# Connectors.net
KiCad netlist of a schematic drawn in Altium Designer
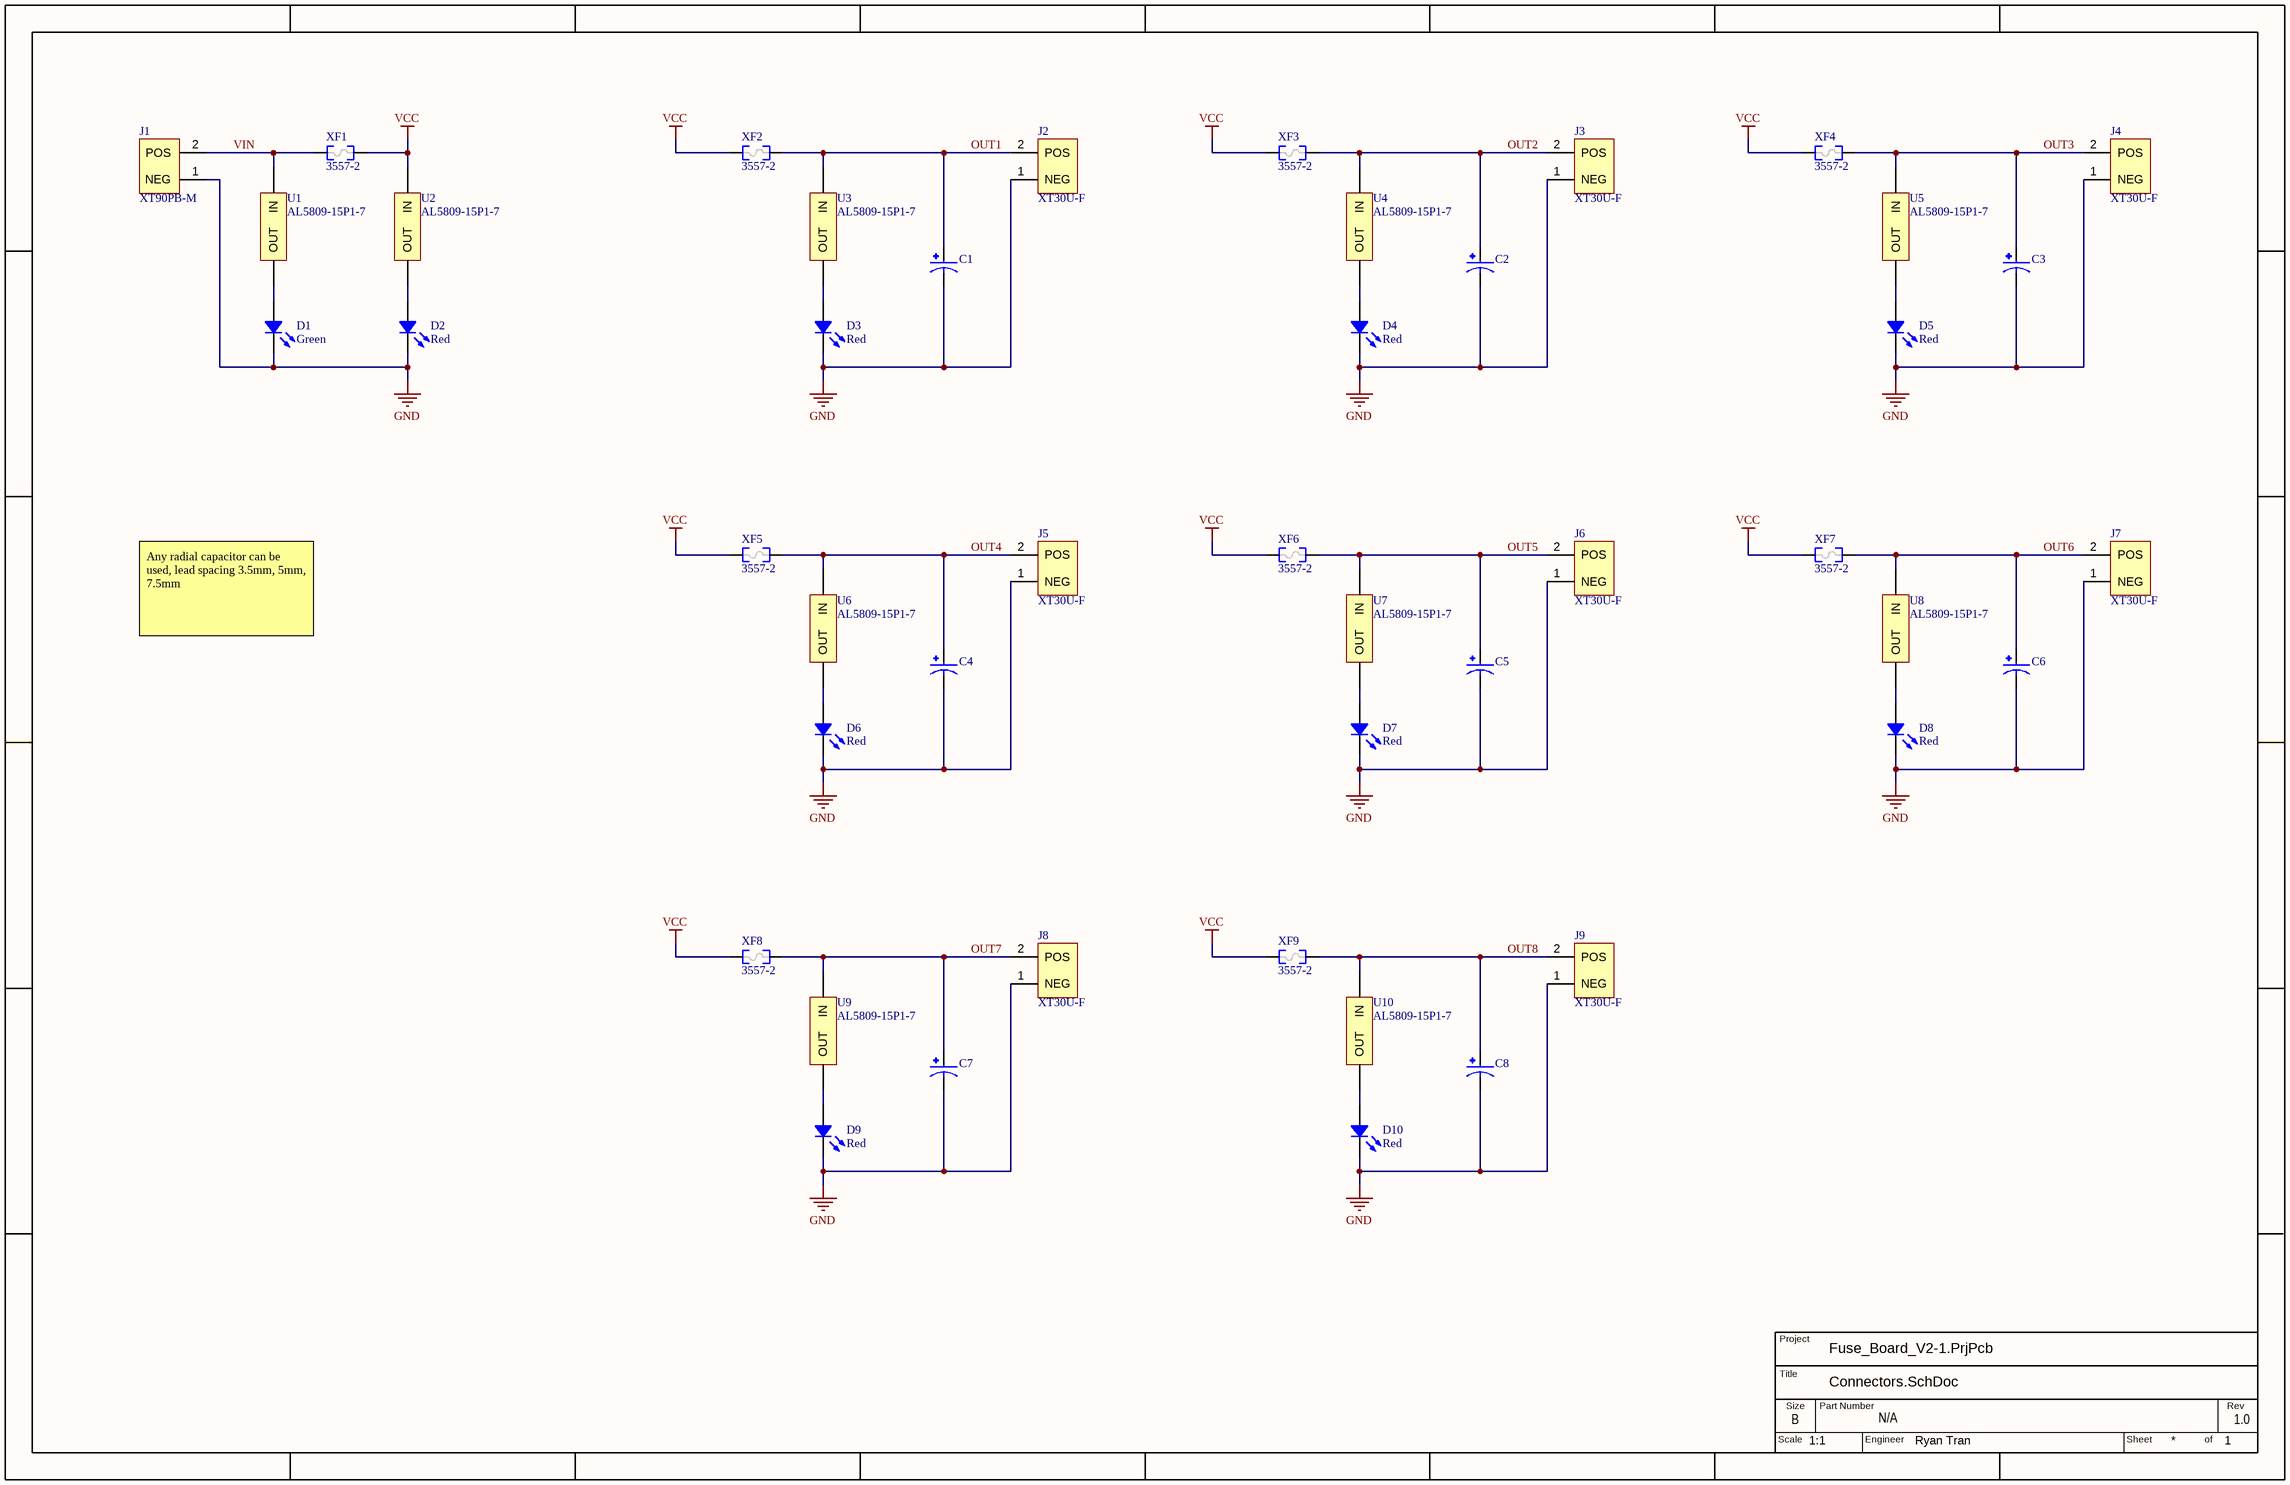
[diagram p0: Connectors.SchDoc]

(export (version "E")
  (design (tool "Eeschema 10.0.6"))
  (components
    (comp (ref "C1")
      (value "Capacitor Generic")
      (footprint "RADIAL_CAP_10mm")
      (description "Cap Radial Aluminum Cylindrical Can 3.5mm, 5mm")
      (fields (field (name "MF") "Panasonic") (field (name "MP") "ECA-2WHG220"))
      (libsource (lib "Fuse_Board_Symbols") (part "Capacitor Generic"))
    )
    (comp (ref "C2")
      (value "Capacitor Generic")
      (footprint "RADIAL_CAP_10mm")
      (description "Cap Radial Aluminum Cylindrical Can 3.5mm, 5mm")
      (fields (field (name "MF") "Panasonic") (field (name "MP") "ECA-2WHG220"))
      (libsource (lib "Fuse_Board_Symbols") (part "Capacitor Generic"))
    )
    (comp (ref "C3")
      (value "Capacitor Generic")
      (footprint "RADIAL_CAP_10mm")
      (description "Cap Radial Aluminum Cylindrical Can 3.5mm, 5mm")
      (fields (field (name "MF") "Panasonic") (field (name "MP") "ECA-2WHG220"))
      (libsource (lib "Fuse_Board_Symbols") (part "Capacitor Generic"))
    )
    (comp (ref "C4")
      (value "Capacitor Generic")
      (footprint "RADIAL_CAP_10mm")
      (description "Cap Radial Aluminum Cylindrical Can 3.5mm, 5mm")
      (fields (field (name "MF") "Panasonic") (field (name "MP") "ECA-2WHG220"))
      (libsource (lib "Fuse_Board_Symbols") (part "Capacitor Generic"))
    )
    (comp (ref "C5")
      (value "Capacitor Generic")
      (footprint "RADIAL_CAP_10mm")
      (description "Cap Radial Aluminum Cylindrical Can 3.5mm, 5mm")
      (fields (field (name "MF") "Panasonic") (field (name "MP") "ECA-2WHG220"))
      (libsource (lib "Fuse_Board_Symbols") (part "Capacitor Generic"))
    )
    (comp (ref "C6")
      (value "Capacitor Generic")
      (footprint "RADIAL_CAP_10mm")
      (description "Cap Radial Aluminum Cylindrical Can 3.5mm, 5mm")
      (fields (field (name "MF") "Panasonic") (field (name "MP") "ECA-2WHG220"))
      (libsource (lib "Fuse_Board_Symbols") (part "Capacitor Generic"))
    )
    (comp (ref "C7")
      (value "Capacitor Generic")
      (footprint "RADIAL_CAP_10mm")
      (description "Cap Radial Aluminum Cylindrical Can 3.5mm, 5mm")
      (fields (field (name "MF") "Panasonic") (field (name "MP") "ECA-2WHG220"))
      (libsource (lib "Fuse_Board_Symbols") (part "Capacitor Generic"))
    )
    (comp (ref "C8")
      (value "Capacitor Generic")
      (footprint "RADIAL_CAP_10mm")
      (description "Cap Radial Aluminum Cylindrical Can 3.5mm, 5mm")
      (fields (field (name "MF") "Panasonic") (field (name "MP") "ECA-2WHG220"))
      (libsource (lib "Fuse_Board_Symbols") (part "Capacitor Generic"))
    )
    (comp (ref "D1")
      (value "Green")
      (footprint "LED 0603_1608 GREEN")
      (description "LED GREEN CLEAR CHIP SMD")
      (fields (field (name "PART NUMBER") "LTST-C193TGKT-5A") (field (name "MANUFACTURER") "Lite-On Inc."))
      (libsource (lib "Celestial Altium Library - altium_library") (part "LED"))
    )
    (comp (ref "D2")
      (value "Red")
      (footprint "LED 0603_1608 RED")
      (description "LED RED CLEAR 2SMD")
      (fields
        (field (name "PART NUMBER") "19-217/R6C-AL1M2VY/3T")
        (field (name "MANUFACTURER") "Everlight Electronics Co Ltd")
      )
      (libsource (lib "Celestial Altium Library - altium_library") (part "LED"))
    )
    (comp (ref "D3")
      (value "Red")
      (footprint "LED 0603_1608 RED")
      (description "LED RED CLEAR 2SMD")
      (fields
        (field (name "PART NUMBER") "19-217/R6C-AL1M2VY/3T")
        (field (name "MANUFACTURER") "Everlight Electronics Co Ltd")
      )
      (libsource (lib "Celestial Altium Library - altium_library") (part "LED"))
    )
    (comp (ref "D4")
      (value "Red")
      (footprint "LED 0603_1608 RED")
      (description "LED RED CLEAR 2SMD")
      (fields
        (field (name "PART NUMBER") "19-217/R6C-AL1M2VY/3T")
        (field (name "MANUFACTURER") "Everlight Electronics Co Ltd")
      )
      (libsource (lib "Celestial Altium Library - altium_library") (part "LED"))
    )
    (comp (ref "D5")
      (value "Red")
      (footprint "LED 0603_1608 RED")
      (description "LED RED CLEAR 2SMD")
      (fields
        (field (name "PART NUMBER") "19-217/R6C-AL1M2VY/3T")
        (field (name "MANUFACTURER") "Everlight Electronics Co Ltd")
      )
      (libsource (lib "Celestial Altium Library - altium_library") (part "LED"))
    )
    (comp (ref "D6")
      (value "Red")
      (footprint "LED 0603_1608 RED")
      (description "LED RED CLEAR 2SMD")
      (fields
        (field (name "PART NUMBER") "19-217/R6C-AL1M2VY/3T")
        (field (name "MANUFACTURER") "Everlight Electronics Co Ltd")
      )
      (libsource (lib "Celestial Altium Library - altium_library") (part "LED"))
    )
    (comp (ref "D7")
      (value "Red")
      (footprint "LED 0603_1608 RED")
      (description "LED RED CLEAR 2SMD")
      (fields
        (field (name "PART NUMBER") "19-217/R6C-AL1M2VY/3T")
        (field (name "MANUFACTURER") "Everlight Electronics Co Ltd")
      )
      (libsource (lib "Celestial Altium Library - altium_library") (part "LED"))
    )
    (comp (ref "D8")
      (value "Red")
      (footprint "LED 0603_1608 RED")
      (description "LED RED CLEAR 2SMD")
      (fields
        (field (name "PART NUMBER") "19-217/R6C-AL1M2VY/3T")
        (field (name "MANUFACTURER") "Everlight Electronics Co Ltd")
      )
      (libsource (lib "Celestial Altium Library - altium_library") (part "LED"))
    )
    (comp (ref "D9")
      (value "Red")
      (footprint "LED 0603_1608 RED")
      (description "LED RED CLEAR 2SMD")
      (fields
        (field (name "PART NUMBER") "19-217/R6C-AL1M2VY/3T")
        (field (name "MANUFACTURER") "Everlight Electronics Co Ltd")
      )
      (libsource (lib "Celestial Altium Library - altium_library") (part "LED"))
    )
    (comp (ref "D10")
      (value "Red")
      (footprint "LED 0603_1608 RED")
      (description "LED RED CLEAR 2SMD")
      (fields
        (field (name "PART NUMBER") "19-217/R6C-AL1M2VY/3T")
        (field (name "MANUFACTURER") "Everlight Electronics Co Ltd")
      )
      (libsource (lib "Celestial Altium Library - altium_library") (part "LED"))
    )
    (comp (ref "J1")
      (value "XT90PB-M")
      (footprint "XT90PB-M")
      (description "Plug; DC supply; XT90; male; PIN: 2; for cable; soldered; 30A; 500V")
      (fields (field (name "MP") "XT60-M") (field (name "MF") "AMASS"))
      (libsource (lib "Fuse_Board_Symbols") (part "XT90PB-M"))
    )
    (comp (ref "J2")
      (value "XT30U-F")
      (footprint "AMASS_XT30UPB")
      (description "Plug; DC supply; XT30; female; PIN: 2; for cable; soldering; 15A")
      (fields (field (name "MP") "XT60-M") (field (name "MF") "AMASS"))
      (libsource (lib "Fuse_Board_Symbols_V2-1") (part "XT30U-F"))
    )
    (comp (ref "J3")
      (value "XT30U-F")
      (footprint "AMASS_XT30UPB")
      (description "Plug; DC supply; XT30; female; PIN: 2; for cable; soldering; 15A")
      (fields (field (name "MP") "XT60-M") (field (name "MF") "AMASS"))
      (libsource (lib "Fuse_Board_Symbols_V2-1") (part "XT30U-F"))
    )
    (comp (ref "J4")
      (value "XT30U-F")
      (footprint "AMASS_XT30UPB")
      (description "Plug; DC supply; XT30; female; PIN: 2; for cable; soldering; 15A")
      (fields (field (name "MP") "XT60-M") (field (name "MF") "AMASS"))
      (libsource (lib "Fuse_Board_Symbols_V2-1") (part "XT30U-F"))
    )
    (comp (ref "J5")
      (value "XT30U-F")
      (footprint "AMASS_XT30UPB")
      (description "Plug; DC supply; XT30; female; PIN: 2; for cable; soldering; 15A")
      (fields (field (name "MP") "XT60-M") (field (name "MF") "AMASS"))
      (libsource (lib "Fuse_Board_Symbols_V2-1") (part "XT30U-F"))
    )
    (comp (ref "J6")
      (value "XT30U-F")
      (footprint "AMASS_XT30UPB")
      (description "Plug; DC supply; XT30; female; PIN: 2; for cable; soldering; 15A")
      (fields (field (name "MP") "XT60-M") (field (name "MF") "AMASS"))
      (libsource (lib "Fuse_Board_Symbols_V2-1") (part "XT30U-F"))
    )
    (comp (ref "J7")
      (value "XT30U-F")
      (footprint "AMASS_XT30UPB")
      (description "Plug; DC supply; XT30; female; PIN: 2; for cable; soldering; 15A")
      (fields (field (name "MP") "XT60-M") (field (name "MF") "AMASS"))
      (libsource (lib "Fuse_Board_Symbols_V2-1") (part "XT30U-F"))
    )
    (comp (ref "J8")
      (value "XT30U-F")
      (footprint "AMASS_XT30UPB")
      (description "Plug; DC supply; XT30; female; PIN: 2; for cable; soldering; 15A")
      (fields (field (name "MP") "XT60-M") (field (name "MF") "AMASS"))
      (libsource (lib "Fuse_Board_Symbols_V2-1") (part "XT30U-F"))
    )
    (comp (ref "J9")
      (value "XT30U-F")
      (footprint "AMASS_XT30UPB")
      (description "Plug; DC supply; XT30; female; PIN: 2; for cable; soldering; 15A")
      (fields (field (name "MP") "XT60-M") (field (name "MF") "AMASS"))
      (libsource (lib "Fuse_Board_Symbols_V2-1") (part "XT30U-F"))
    )
    (comp (ref "U1")
      (value "AL5809-15P1-7")
      (footprint "POWERDI_123")
      (description "LED Driver IC 1 Output Linear - PWM Dimming 15mA PowerDI™ 123")
      (libsource (lib "Fuse_Board_Symbols") (part "AL5809-15P1-7"))
    )
    (comp (ref "U2")
      (value "AL5809-15P1-7")
      (footprint "POWERDI_123")
      (description "LED Driver IC 1 Output Linear - PWM Dimming 15mA PowerDI™ 123")
      (libsource (lib "Fuse_Board_Symbols") (part "AL5809-15P1-7"))
    )
    (comp (ref "U3")
      (value "AL5809-15P1-7")
      (footprint "POWERDI_123")
      (description "LED Driver IC 1 Output Linear - PWM Dimming 15mA PowerDI™ 123")
      (libsource (lib "Fuse_Board_Symbols") (part "AL5809-15P1-7"))
    )
    (comp (ref "U4")
      (value "AL5809-15P1-7")
      (footprint "POWERDI_123")
      (description "LED Driver IC 1 Output Linear - PWM Dimming 15mA PowerDI™ 123")
      (libsource (lib "Fuse_Board_Symbols") (part "AL5809-15P1-7"))
    )
    (comp (ref "U5")
      (value "AL5809-15P1-7")
      (footprint "POWERDI_123")
      (description "LED Driver IC 1 Output Linear - PWM Dimming 15mA PowerDI™ 123")
      (libsource (lib "Fuse_Board_Symbols") (part "AL5809-15P1-7"))
    )
    (comp (ref "U6")
      (value "AL5809-15P1-7")
      (footprint "POWERDI_123")
      (description "LED Driver IC 1 Output Linear - PWM Dimming 15mA PowerDI™ 123")
      (libsource (lib "Fuse_Board_Symbols") (part "AL5809-15P1-7"))
    )
    (comp (ref "U7")
      (value "AL5809-15P1-7")
      (footprint "POWERDI_123")
      (description "LED Driver IC 1 Output Linear - PWM Dimming 15mA PowerDI™ 123")
      (libsource (lib "Fuse_Board_Symbols") (part "AL5809-15P1-7"))
    )
    (comp (ref "U8")
      (value "AL5809-15P1-7")
      (footprint "POWERDI_123")
      (description "LED Driver IC 1 Output Linear - PWM Dimming 15mA PowerDI™ 123")
      (libsource (lib "Fuse_Board_Symbols") (part "AL5809-15P1-7"))
    )
    (comp (ref "U9")
      (value "AL5809-15P1-7")
      (footprint "POWERDI_123")
      (description "LED Driver IC 1 Output Linear - PWM Dimming 15mA PowerDI™ 123")
      (libsource (lib "Fuse_Board_Symbols") (part "AL5809-15P1-7"))
    )
    (comp (ref "U10")
      (value "AL5809-15P1-7")
      (footprint "POWERDI_123")
      (description "LED Driver IC 1 Output Linear - PWM Dimming 15mA PowerDI™ 123")
      (libsource (lib "Fuse_Board_Symbols") (part "AL5809-15P1-7"))
    )
    (comp (ref "XF1")
      (value "3557-2")
      (footprint "FUSE_3557-2")
      (description "Fuse Block 30A 500V 1 Circuit Blade Through Hole")
      (fields (field (name "MF") "Keystone Electronics"))
      (libsource (lib "XT60-30_Fuse_Board_Symbols") (part "3557-2"))
    )
    (comp (ref "XF2")
      (value "3557-2")
      (footprint "FUSE_3557-2")
      (description "Fuse Block 30A 500V 1 Circuit Blade Through Hole")
      (fields (field (name "MF") "Keystone Electronics"))
      (libsource (lib "XT60-30_Fuse_Board_Symbols") (part "3557-2"))
    )
    (comp (ref "XF3")
      (value "3557-2")
      (footprint "FUSE_3557-2")
      (description "Fuse Block 30A 500V 1 Circuit Blade Through Hole")
      (fields (field (name "MF") "Keystone Electronics"))
      (libsource (lib "XT60-30_Fuse_Board_Symbols") (part "3557-2"))
    )
    (comp (ref "XF4")
      (value "3557-2")
      (footprint "FUSE_3557-2")
      (description "Fuse Block 30A 500V 1 Circuit Blade Through Hole")
      (fields (field (name "MF") "Keystone Electronics"))
      (libsource (lib "XT60-30_Fuse_Board_Symbols") (part "3557-2"))
    )
    (comp (ref "XF5")
      (value "3557-2")
      (footprint "FUSE_3557-2")
      (description "Fuse Block 30A 500V 1 Circuit Blade Through Hole")
      (fields (field (name "MF") "Keystone Electronics"))
      (libsource (lib "XT60-30_Fuse_Board_Symbols") (part "3557-2"))
    )
    (comp (ref "XF6")
      (value "3557-2")
      (footprint "FUSE_3557-2")
      (description "Fuse Block 30A 500V 1 Circuit Blade Through Hole")
      (fields (field (name "MF") "Keystone Electronics"))
      (libsource (lib "XT60-30_Fuse_Board_Symbols") (part "3557-2"))
    )
    (comp (ref "XF7")
      (value "3557-2")
      (footprint "FUSE_3557-2")
      (description "Fuse Block 30A 500V 1 Circuit Blade Through Hole")
      (fields (field (name "MF") "Keystone Electronics"))
      (libsource (lib "XT60-30_Fuse_Board_Symbols") (part "3557-2"))
    )
    (comp (ref "XF8")
      (value "3557-2")
      (footprint "FUSE_3557-2")
      (description "Fuse Block 30A 500V 1 Circuit Blade Through Hole")
      (fields (field (name "MF") "Keystone Electronics"))
      (libsource (lib "XT60-30_Fuse_Board_Symbols") (part "3557-2"))
    )
    (comp (ref "XF9")
      (value "3557-2")
      (footprint "FUSE_3557-2")
      (description "Fuse Block 30A 500V 1 Circuit Blade Through Hole")
      (fields (field (name "MF") "Keystone Electronics"))
      (libsource (lib "XT60-30_Fuse_Board_Symbols") (part "3557-2"))
    )
  )
  (nets
    (net (code "1") (name "/OUT1") (class "Default")
      (node (ref "C1") (pin "2") (pinfunction "2_2") (pintype "passive"))
      (node (ref "J2") (pin "2") (pinfunction "POS_2") (pintype "passive"))
      (node (ref "U3") (pin "1") (pinfunction "IN_1") (pintype "passive"))
      (node (ref "XF2") (pin "2") (pinfunction "2_2") (pintype "passive"))
    )
    (net (code "2") (name "/OUT2") (class "Default")
      (node (ref "C2") (pin "2") (pinfunction "2_2") (pintype "passive"))
      (node (ref "J3") (pin "2") (pinfunction "POS_2") (pintype "passive"))
      (node (ref "U4") (pin "1") (pinfunction "IN_1") (pintype "passive"))
      (node (ref "XF3") (pin "2") (pinfunction "2_2") (pintype "passive"))
    )
    (net (code "3") (name "/OUT3") (class "Default")
      (node (ref "C3") (pin "2") (pinfunction "2_2") (pintype "passive"))
      (node (ref "J4") (pin "2") (pinfunction "POS_2") (pintype "passive"))
      (node (ref "U5") (pin "1") (pinfunction "IN_1") (pintype "passive"))
      (node (ref "XF4") (pin "2") (pinfunction "2_2") (pintype "passive"))
    )
    (net (code "4") (name "/OUT4") (class "Default")
      (node (ref "C4") (pin "2") (pinfunction "2_2") (pintype "passive"))
      (node (ref "J5") (pin "2") (pinfunction "POS_2") (pintype "passive"))
      (node (ref "U6") (pin "1") (pinfunction "IN_1") (pintype "passive"))
      (node (ref "XF5") (pin "2") (pinfunction "2_2") (pintype "passive"))
    )
    (net (code "5") (name "/OUT5") (class "Default")
      (node (ref "C5") (pin "2") (pinfunction "2_2") (pintype "passive"))
      (node (ref "J6") (pin "2") (pinfunction "POS_2") (pintype "passive"))
      (node (ref "U7") (pin "1") (pinfunction "IN_1") (pintype "passive"))
      (node (ref "XF6") (pin "2") (pinfunction "2_2") (pintype "passive"))
    )
    (net (code "6") (name "/OUT6") (class "Default")
      (node (ref "C6") (pin "2") (pinfunction "2_2") (pintype "passive"))
      (node (ref "J7") (pin "2") (pinfunction "POS_2") (pintype "passive"))
      (node (ref "U8") (pin "1") (pinfunction "IN_1") (pintype "passive"))
      (node (ref "XF7") (pin "2") (pinfunction "2_2") (pintype "passive"))
    )
    (net (code "7") (name "/OUT7") (class "Default")
      (node (ref "C7") (pin "2") (pinfunction "2_2") (pintype "passive"))
      (node (ref "J8") (pin "2") (pinfunction "POS_2") (pintype "passive"))
      (node (ref "U9") (pin "1") (pinfunction "IN_1") (pintype "passive"))
      (node (ref "XF8") (pin "2") (pinfunction "2_2") (pintype "passive"))
    )
    (net (code "8") (name "/OUT8") (class "Default")
      (node (ref "C8") (pin "2") (pinfunction "2_2") (pintype "passive"))
      (node (ref "J9") (pin "2") (pinfunction "POS_2") (pintype "passive"))
      (node (ref "U10") (pin "1") (pinfunction "IN_1") (pintype "passive"))
      (node (ref "XF9") (pin "2") (pinfunction "2_2") (pintype "passive"))
    )
    (net (code "9") (name "/VIN") (class "Default")
      (node (ref "J1") (pin "2") (pinfunction "POS_2") (pintype "passive"))
      (node (ref "U1") (pin "1") (pinfunction "IN_1") (pintype "passive"))
      (node (ref "XF1") (pin "1") (pinfunction "1_1") (pintype "passive"))
    )
    (net (code "10") (name "GND") (class "Default")
      (node (ref "C1") (pin "1") (pinfunction "1_1") (pintype "passive"))
      (node (ref "C2") (pin "1") (pinfunction "1_1") (pintype "passive"))
      (node (ref "C3") (pin "1") (pinfunction "1_1") (pintype "passive"))
      (node (ref "C4") (pin "1") (pinfunction "1_1") (pintype "passive"))
      (node (ref "C5") (pin "1") (pinfunction "1_1") (pintype "passive"))
      (node (ref "C6") (pin "1") (pinfunction "1_1") (pintype "passive"))
      (node (ref "C7") (pin "1") (pinfunction "1_1") (pintype "passive"))
      (node (ref "C8") (pin "1") (pinfunction "1_1") (pintype "passive"))
      (node (ref "D1") (pin "2") (pinfunction "2_2") (pintype "passive"))
      (node (ref "D10") (pin "2") (pinfunction "2_2") (pintype "passive"))
      (node (ref "D2") (pin "2") (pinfunction "2_2") (pintype "passive"))
      (node (ref "D3") (pin "2") (pinfunction "2_2") (pintype "passive"))
      (node (ref "D4") (pin "2") (pinfunction "2_2") (pintype "passive"))
      (node (ref "D5") (pin "2") (pinfunction "2_2") (pintype "passive"))
      (node (ref "D6") (pin "2") (pinfunction "2_2") (pintype "passive"))
      (node (ref "D7") (pin "2") (pinfunction "2_2") (pintype "passive"))
      (node (ref "D8") (pin "2") (pinfunction "2_2") (pintype "passive"))
      (node (ref "D9") (pin "2") (pinfunction "2_2") (pintype "passive"))
      (node (ref "J1") (pin "1") (pinfunction "NEG_1") (pintype "passive"))
      (node (ref "J2") (pin "1") (pinfunction "NEG_1") (pintype "passive"))
      (node (ref "J3") (pin "1") (pinfunction "NEG_1") (pintype "passive"))
      (node (ref "J4") (pin "1") (pinfunction "NEG_1") (pintype "passive"))
      (node (ref "J5") (pin "1") (pinfunction "NEG_1") (pintype "passive"))
      (node (ref "J6") (pin "1") (pinfunction "NEG_1") (pintype "passive"))
      (node (ref "J7") (pin "1") (pinfunction "NEG_1") (pintype "passive"))
      (node (ref "J8") (pin "1") (pinfunction "NEG_1") (pintype "passive"))
      (node (ref "J9") (pin "1") (pinfunction "NEG_1") (pintype "passive"))
    )
    (net (code "11") (name "Net-(U1-OUT)") (class "Default")
      (node (ref "D1") (pin "1") (pinfunction "1_1") (pintype "passive"))
      (node (ref "U1") (pin "2") (pinfunction "OUT_2") (pintype "passive"))
    )
    (net (code "12") (name "Net-(U2-OUT)") (class "Default")
      (node (ref "D2") (pin "1") (pinfunction "1_1") (pintype "passive"))
      (node (ref "U2") (pin "2") (pinfunction "OUT_2") (pintype "passive"))
    )
    (net (code "13") (name "Net-(U3-OUT)") (class "Default")
      (node (ref "D3") (pin "1") (pinfunction "1_1") (pintype "passive"))
      (node (ref "U3") (pin "2") (pinfunction "OUT_2") (pintype "passive"))
    )
    (net (code "14") (name "Net-(U4-OUT)") (class "Default")
      (node (ref "D4") (pin "1") (pinfunction "1_1") (pintype "passive"))
      (node (ref "U4") (pin "2") (pinfunction "OUT_2") (pintype "passive"))
    )
    (net (code "15") (name "Net-(U5-OUT)") (class "Default")
      (node (ref "D5") (pin "1") (pinfunction "1_1") (pintype "passive"))
      (node (ref "U5") (pin "2") (pinfunction "OUT_2") (pintype "passive"))
    )
    (net (code "16") (name "Net-(U6-OUT)") (class "Default")
      (node (ref "D6") (pin "1") (pinfunction "1_1") (pintype "passive"))
      (node (ref "U6") (pin "2") (pinfunction "OUT_2") (pintype "passive"))
    )
    (net (code "17") (name "Net-(U7-OUT)") (class "Default")
      (node (ref "D7") (pin "1") (pinfunction "1_1") (pintype "passive"))
      (node (ref "U7") (pin "2") (pinfunction "OUT_2") (pintype "passive"))
    )
    (net (code "18") (name "Net-(U8-OUT)") (class "Default")
      (node (ref "D8") (pin "1") (pinfunction "1_1") (pintype "passive"))
      (node (ref "U8") (pin "2") (pinfunction "OUT_2") (pintype "passive"))
    )
    (net (code "19") (name "Net-(U9-OUT)") (class "Default")
      (node (ref "D9") (pin "1") (pinfunction "1_1") (pintype "passive"))
      (node (ref "U9") (pin "2") (pinfunction "OUT_2") (pintype "passive"))
    )
    (net (code "20") (name "Net-(U10-OUT)") (class "Default")
      (node (ref "D10") (pin "1") (pinfunction "1_1") (pintype "passive"))
      (node (ref "U10") (pin "2") (pinfunction "OUT_2") (pintype "passive"))
    )
    (net (code "21") (name "VCC") (class "Default")
      (node (ref "U2") (pin "1") (pinfunction "IN_1") (pintype "passive"))
      (node (ref "XF1") (pin "2") (pinfunction "2_2") (pintype "passive"))
      (node (ref "XF2") (pin "1") (pinfunction "1_1") (pintype "passive"))
      (node (ref "XF3") (pin "1") (pinfunction "1_1") (pintype "passive"))
      (node (ref "XF4") (pin "1") (pinfunction "1_1") (pintype "passive"))
      (node (ref "XF5") (pin "1") (pinfunction "1_1") (pintype "passive"))
      (node (ref "XF6") (pin "1") (pinfunction "1_1") (pintype "passive"))
      (node (ref "XF7") (pin "1") (pinfunction "1_1") (pintype "passive"))
      (node (ref "XF8") (pin "1") (pinfunction "1_1") (pintype "passive"))
      (node (ref "XF9") (pin "1") (pinfunction "1_1") (pintype "passive"))
    )
  )
)
